# SENSOR.net
KiCad netlist of a schematic drawn in Altium Designer
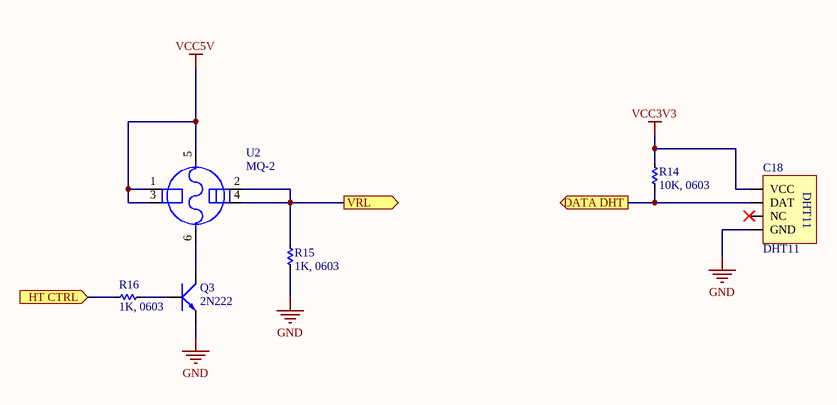
[diagram p0: SENSOR.SchDoc]

(export (version "E")
  (design (tool "Eeschema 10.0.6"))
  (components
    (comp (ref "C18")
      (value "DHT11")
      (footprint "DHT11")
      (fields
        (field (name "MANUFACTURER") "Würth Elektronik eiSos GmbH")
        (field (name "PARTNO") "613004143121")
        (field (name "CREATED BY") "Karrer Zheng")
      )
      (libsource (lib "KhanhBK_SCH_Library_1") (part "DHT11"))
    )
    (comp (ref "Q3")
      (value "2N222")
      (footprint "TO92-123")
      (description "NPN 600mW, ECB")
      (libsource (lib "KhanhBK_SCH_Library_1") (part "2N222"))
    )
    (comp (ref "R14")
      (value "10K, 0603")
      (footprint "RES-SMD-0603")
      (description "Resistor")
      (fields
        (field (name "MANUFACTURER") "Generic Components")
        (field (name "PUBLISHER") "Altium Hobart Technology Centre")
      )
      (libsource (lib "KhanhBK_SCH_Library_1") (part "Res-SMD"))
    )
    (comp (ref "R15")
      (value "1K, 0603")
      (footprint "RES-SMD-0603")
      (description "Resistor")
      (fields
        (field (name "MANUFACTURER") "Generic Components")
        (field (name "PUBLISHER") "Altium Hobart Technology Centre")
      )
      (libsource (lib "KhanhBK_SCH_Library_1") (part "Res-SMD"))
    )
    (comp (ref "R16")
      (value "1K, 0603")
      (footprint "RES-SMD-0603")
      (description "Resistor")
      (fields
        (field (name "MANUFACTURER") "Generic Components")
        (field (name "PUBLISHER") "Altium Hobart Technology Centre")
      )
      (libsource (lib "KhanhBK_SCH_Library_1") (part "Res-SMD"))
    )
    (comp (ref "U2")
      (value "MQ-2")
      (footprint "SNR6-D19.0MM")
      (description "314100003")
      (fields (field (name "MF") "{'manufacturer': u'AirBorn'}"))
      (libsource (lib "SnapEDA_Library") (part "DIP-GAS-MQ-2(6P-D19MM)"))
    )
  )
  (nets
    (net (code "1") (name "/DATA DHT") (class "Default")
      (node (ref "C18") (pin "2") (pinfunction "DAT_2") (pintype "passive"))
      (node (ref "R14") (pin "1") (pinfunction "1_1") (pintype "passive"))
    )
    (net (code "2") (name "/HT CTRL") (class "Default")
      (node (ref "R16") (pin "2") (pinfunction "2_2") (pintype "passive"))
    )
    (net (code "3") (name "/VRL") (class "Default")
      (node (ref "R15") (pin "1") (pinfunction "1_1") (pintype "passive"))
      (node (ref "U2") (pin "2") (pinfunction "B0_2") (pintype "bidirectional"))
      (node (ref "U2") (pin "4") (pinfunction "B1_4") (pintype "bidirectional"))
    )
    (net (code "4") (name "GND") (class "Default")
      (node (ref "C18") (pin "4") (pinfunction "GND_4") (pintype "passive"))
      (node (ref "Q3") (pin "1") (pinfunction "E_1") (pintype "passive"))
      (node (ref "R15") (pin "2") (pinfunction "2_2") (pintype "passive"))
    )
    (net (code "5") (name "Net-(Q3-B)") (class "Default")
      (node (ref "Q3") (pin "2") (pinfunction "B_2") (pintype "passive"))
      (node (ref "R16") (pin "1") (pinfunction "1_1") (pintype "passive"))
    )
    (net (code "6") (name "Net-(Q3-C)") (class "Default")
      (node (ref "Q3") (pin "3") (pinfunction "C_3") (pintype "passive"))
      (node (ref "U2") (pin "6") (pinfunction "H@2_6") (pintype "bidirectional"))
    )
    (net (code "7") (name "VCC3V3") (class "Default")
      (node (ref "C18") (pin "1") (pinfunction "VCC_1") (pintype "passive"))
      (node (ref "R14") (pin "2") (pinfunction "2_2") (pintype "passive"))
    )
    (net (code "8") (name "VCC5V") (class "Default")
      (node (ref "U2") (pin "1") (pinfunction "A0_1") (pintype "bidirectional"))
      (node (ref "U2") (pin "3") (pinfunction "A1_3") (pintype "bidirectional"))
      (node (ref "U2") (pin "5") (pinfunction "H@1_5") (pintype "bidirectional"))
    )
    (net (code "9") (name "unconnected-(C18-NC-Pad3)") (class "Default")
      (node (ref "C18") (pin "3") (pinfunction "NC_3") (pintype "passive+no_connect"))
    )
  )
)
